# 2_INTERFACES_EXTERNAS.net
KiCad netlist of a schematic drawn in Altium Designer
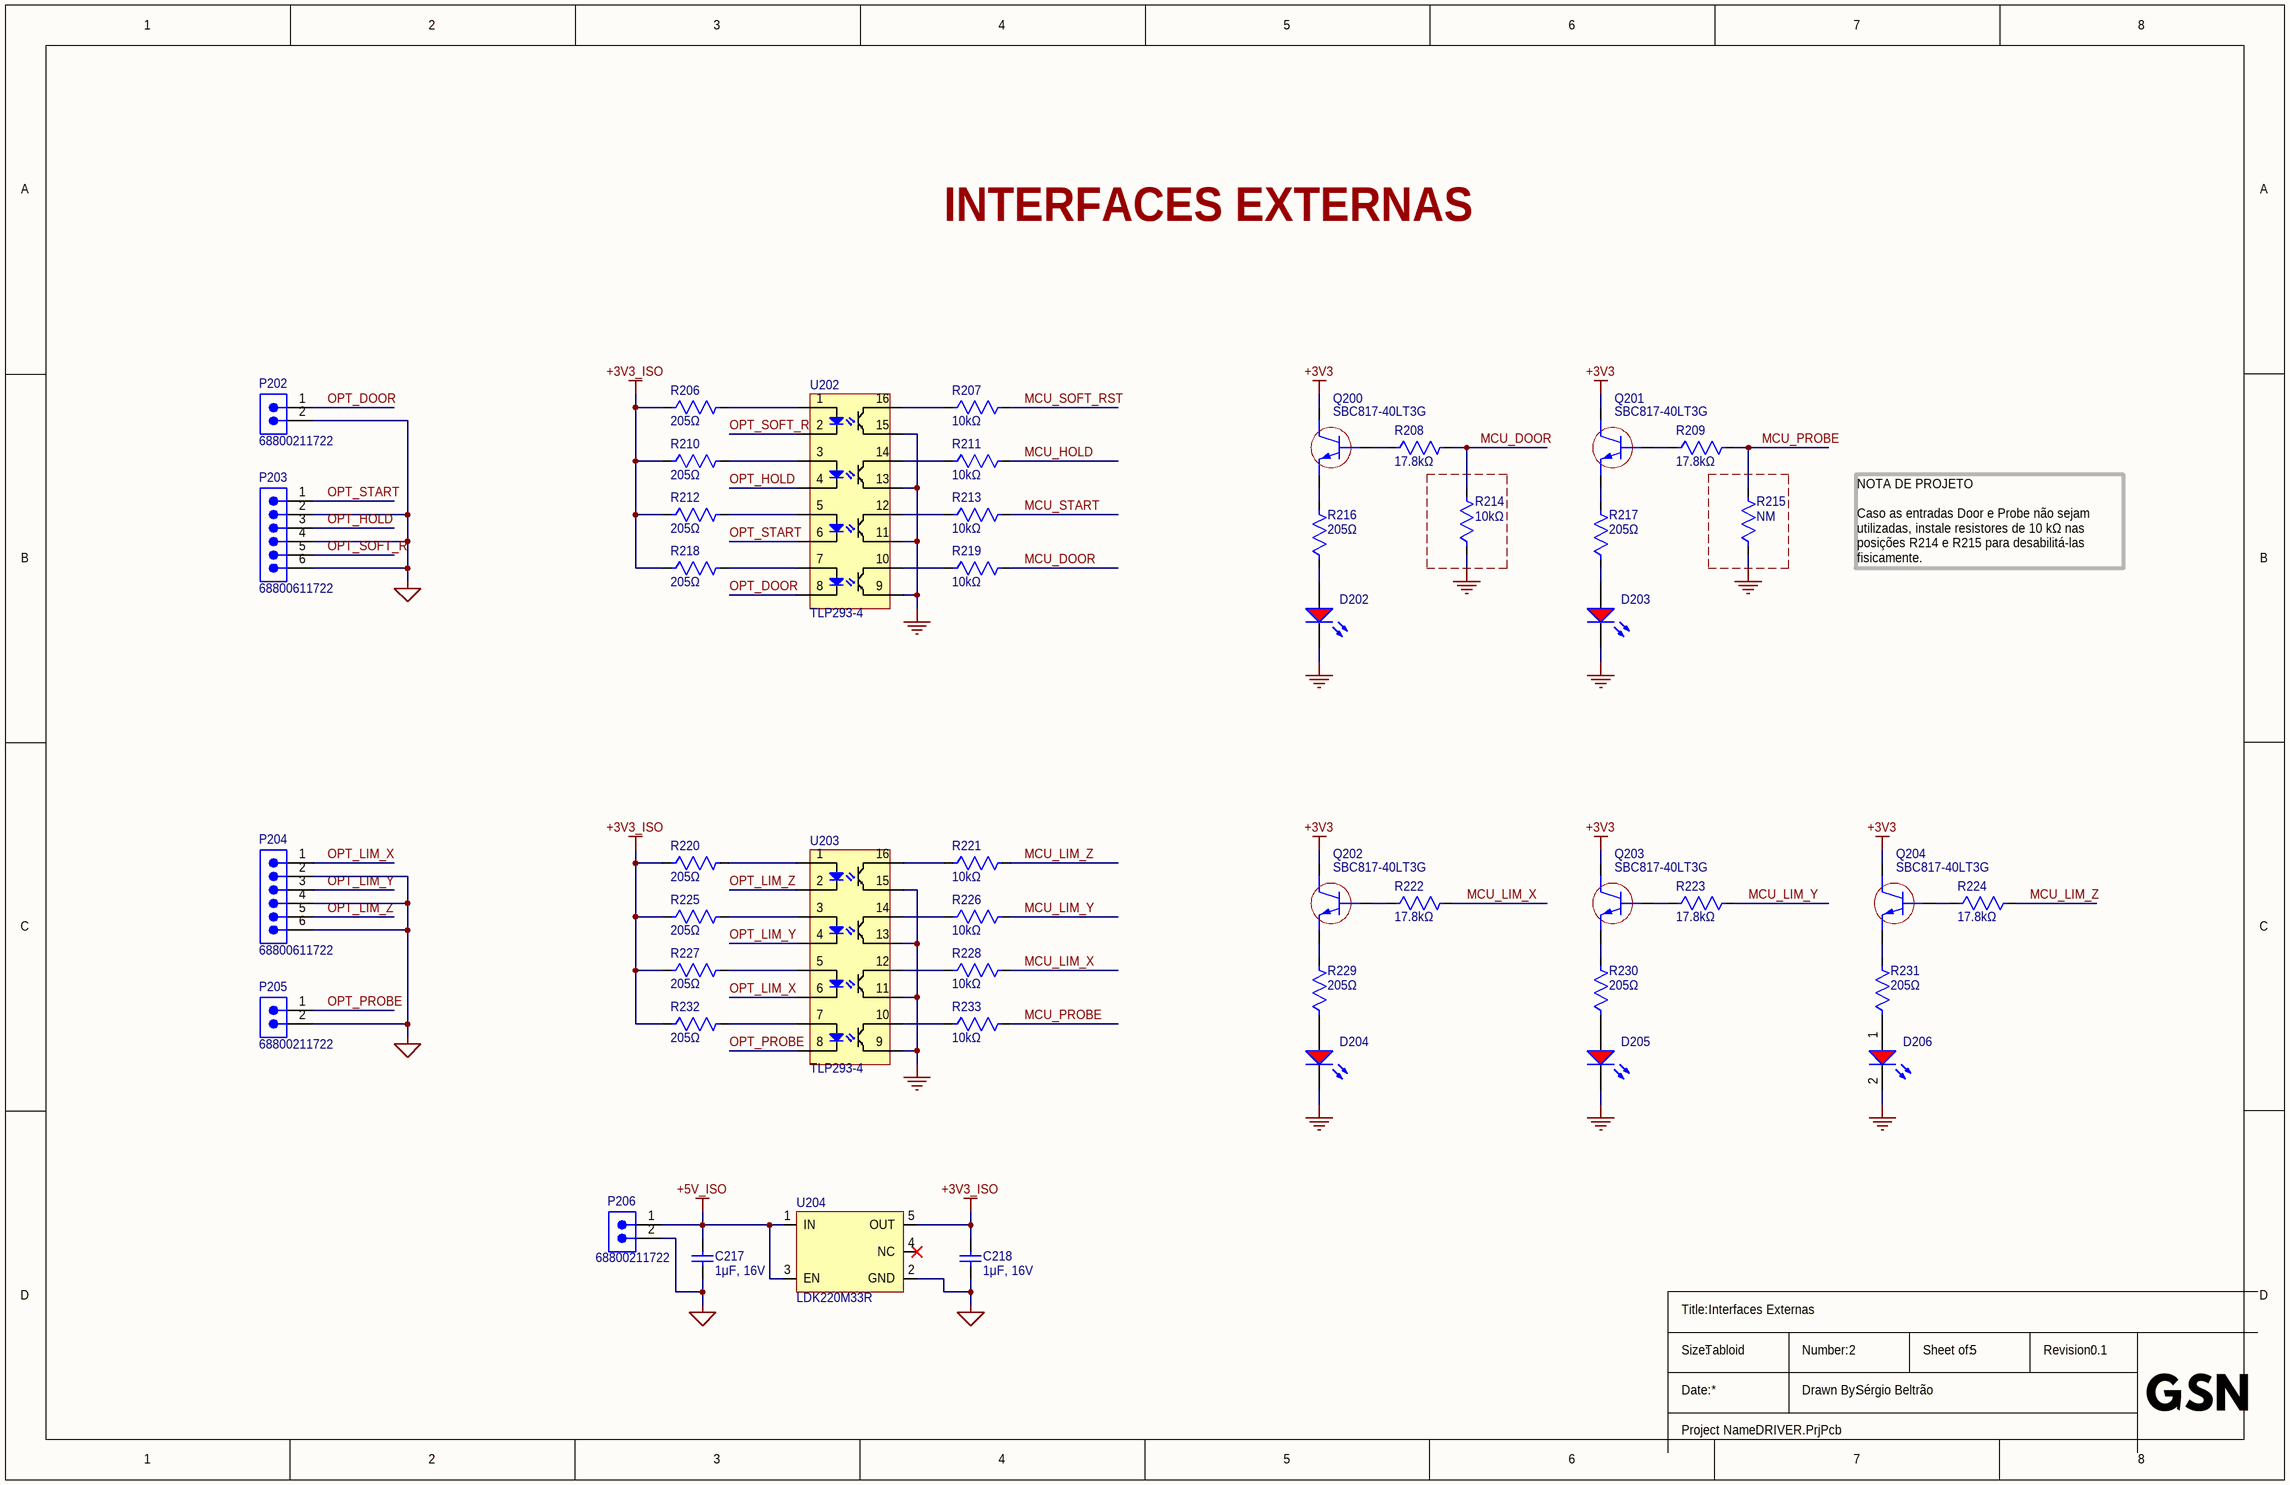
[diagram p0: 2_INTERFACES_EXTERNAS.SchDoc]

(export (version "E")
  (design (tool "Eeschema 10.0.6"))
  (components
    (comp (ref "C217")
      (value "1μF, 16V")
      (footprint "WCAP-CSGP_0603_L1.6W0.8H0.8_Wave")
      (description "WCAP-CSGP Multilayer Ceramic Chip Capacitor, General Purpose, size 0603, 1μF, 16V")
      (fields
        (field (name "MANUFACTURER PART NUMBER") "885012206052")
        (field (name "MANUFACTURER") "Wurth Elektronik")
      )
      (libsource (lib "WE - Passive Components") (part "Capacitor_Non-Polarized"))
    )
    (comp (ref "C218")
      (value "1μF, 16V")
      (footprint "WCAP-CSGP_0603_L1.6W0.8H0.8_Wave")
      (description "WCAP-CSGP Multilayer Ceramic Chip Capacitor, General Purpose, size 0603, 1μF, 16V")
      (fields
        (field (name "MANUFACTURER PART NUMBER") "885012206052")
        (field (name "MANUFACTURER") "Wurth Elektronik")
      )
      (libsource (lib "WE - Passive Components") (part "Capacitor_Non-Polarized"))
    )
    (comp (ref "D202")
      (value "Red, 2V, 140deg")
      (footprint "WL-SMCW_0603_150060xx75003")
      (description "WL-SMCW Mono-color Chip LED Waterclear, SMT, size 0603, Red, 2V, 140°")
      (fields
        (field (name "MANUFACTURER PART NUMBER") "150060RS75003")
        (field (name "MANUFACTURER") "Wurth Elektronik")
      )
      (libsource (lib "WE - Optoelectronic Components") (part "LED_Red_1A-2K"))
    )
    (comp (ref "D203")
      (value "Red, 2V, 140deg")
      (footprint "WL-SMCW_0603_150060xx75003")
      (description "WL-SMCW Mono-color Chip LED Waterclear, SMT, size 0603, Red, 2V, 140°")
      (fields
        (field (name "MANUFACTURER PART NUMBER") "150060RS75003")
        (field (name "MANUFACTURER") "Wurth Elektronik")
      )
      (libsource (lib "WE - Optoelectronic Components") (part "LED_Red_1A-2K"))
    )
    (comp (ref "D204")
      (value "Red, 2V, 140deg")
      (footprint "WL-SMCW_0603_150060xx75003")
      (description "WL-SMCW Mono-color Chip LED Waterclear, SMT, size 0603, Red, 2V, 140°")
      (fields
        (field (name "MANUFACTURER PART NUMBER") "150060RS75003")
        (field (name "MANUFACTURER") "Wurth Elektronik")
      )
      (libsource (lib "WE - Optoelectronic Components") (part "LED_Red_1A-2K"))
    )
    (comp (ref "D205")
      (value "Red, 2V, 140deg")
      (footprint "WL-SMCW_0603_150060xx75003")
      (description "WL-SMCW Mono-color Chip LED Waterclear, SMT, size 0603, Red, 2V, 140°")
      (fields
        (field (name "MANUFACTURER PART NUMBER") "150060RS75003")
        (field (name "MANUFACTURER") "Wurth Elektronik")
      )
      (libsource (lib "WE - Optoelectronic Components") (part "LED_Red_1A-2K"))
    )
    (comp (ref "D206")
      (value "Red, 2V, 140deg")
      (footprint "WL-SMCW_0603_150060xx75003")
      (description "WL-SMCW Mono-color Chip LED Waterclear, SMT, size 0603, Red, 2V, 140°")
      (fields
        (field (name "MANUFACTURER PART NUMBER") "150060RS75003")
        (field (name "MANUFACTURER") "Wurth Elektronik")
      )
      (libsource (lib "") (part "LED_Red_1A-2K_1"))
    )
    (comp (ref "P202")
      (value "68800211722")
      (footprint "68800211722")
      (description "WR-WTB “J” Type THT Male Horizontal Shrouded Header, pitch 2.5 mm, 2 pins")
      (fields (field (name "MANUFACTURER") "Wurth Elektronik"))
      (libsource (lib "WE - Electromechanical Components") (part "Header_Male_1R_02P"))
    )
    (comp (ref "P203")
      (value "68800611722")
      (footprint "68800611722")
      (description "WR-WTB “J” Type THT Male Horizontal Shrouded Header, pitch 2.5 mm, 6 pins")
      (fields (field (name "MANUFACTURER") "Wurth Elektronik"))
      (libsource (lib "WE - Electromechanical Components") (part "Header_Male_1R_06P"))
    )
    (comp (ref "P204")
      (value "68800611722")
      (footprint "68800611722")
      (description "WR-WTB “J” Type THT Male Horizontal Shrouded Header, pitch 2.5 mm, 6 pins")
      (fields (field (name "MANUFACTURER") "Wurth Elektronik"))
      (libsource (lib "WE - Electromechanical Components") (part "Header_Male_1R_06P"))
    )
    (comp (ref "P205")
      (value "68800211722")
      (footprint "68800211722")
      (description "WR-WTB “J” Type THT Male Horizontal Shrouded Header, pitch 2.5 mm, 2 pins")
      (fields (field (name "MANUFACTURER") "Wurth Elektronik"))
      (libsource (lib "WE - Electromechanical Components") (part "Header_Male_1R_02P"))
    )
    (comp (ref "P206")
      (value "68800211722")
      (footprint "68800211722")
      (description "WR-WTB “J” Type THT Male Horizontal Shrouded Header, pitch 2.5 mm, 2 pins")
      (fields (field (name "MANUFACTURER") "Wurth Elektronik"))
      (libsource (lib "WE - Electromechanical Components") (part "Header_Male_1R_02P"))
    )
    (comp (ref "Q200")
      (value "SBC817-40LT3G")
      (footprint "SOT-23-3")
      (description "TRANS NPN 45V 0.5A SOT23-3")
      (fields (field (name "MANUFACTURER") "onsemi"))
      (libsource (lib "Transistors") (part "SBC817-40LT3G"))
    )
    (comp (ref "Q201")
      (value "SBC817-40LT3G")
      (footprint "SOT-23-3")
      (description "TRANS NPN 45V 0.5A SOT23-3")
      (fields (field (name "MANUFACTURER") "onsemi"))
      (libsource (lib "Transistors") (part "SBC817-40LT3G"))
    )
    (comp (ref "Q202")
      (value "SBC817-40LT3G")
      (footprint "SOT-23-3")
      (description "TRANS NPN 45V 0.5A SOT23-3")
      (fields (field (name "MANUFACTURER") "onsemi"))
      (libsource (lib "Transistors") (part "SBC817-40LT3G"))
    )
    (comp (ref "Q203")
      (value "SBC817-40LT3G")
      (footprint "SOT-23-3")
      (description "TRANS NPN 45V 0.5A SOT23-3")
      (fields (field (name "MANUFACTURER") "onsemi"))
      (libsource (lib "Transistors") (part "SBC817-40LT3G"))
    )
    (comp (ref "Q204")
      (value "SBC817-40LT3G")
      (footprint "SOT-23-3")
      (description "TRANS NPN 45V 0.5A SOT23-3")
      (fields (field (name "MANUFACTURER") "onsemi"))
      (libsource (lib "Transistors") (part "SBC817-40LT3G"))
    )
    (comp (ref "R206")
      (value "205Ω")
      (footprint "0603-WAVE")
      (description "RES 205 OHM 1% 1/10W 0603")
      (fields
        (field (name "MANUFACTURER PART NUMBER") "RC0603FR-07205RL")
        (field (name "MANUFACTURER") "Yageo Group")
      )
      (libsource (lib "Resistors-0603-E96-Yageo") (part "RC0603FR-07205RL"))
    )
    (comp (ref "R207")
      (value "10kΩ")
      (footprint "0603-WAVE")
      (description "RES 10K OHM 1% 1/10W 0603")
      (fields
        (field (name "MANUFACTURER PART NUMBER") "RC0603FR-0710KL")
        (field (name "MANUFACTURER") "Yageo Group")
      )
      (libsource (lib "Resistors-0603-E96-Yageo") (part "RC0603FR-0710KL"))
    )
    (comp (ref "R208")
      (value "17.8kΩ")
      (footprint "0603-WAVE")
      (description "RES 17.8K OHM 1% 1/10W 0603")
      (fields
        (field (name "MANUFACTURER PART NUMBER") "RC0603FR-0717K8L")
        (field (name "MANUFACTURER") "Yageo Group")
      )
      (libsource (lib "Resistors-0603-E96-Yageo") (part "RC0603FR-0717K8L"))
    )
    (comp (ref "R209")
      (value "17.8kΩ")
      (footprint "0603-WAVE")
      (description "RES 17.8K OHM 1% 1/10W 0603")
      (fields
        (field (name "MANUFACTURER PART NUMBER") "RC0603FR-0717K8L")
        (field (name "MANUFACTURER") "Yageo Group")
      )
      (libsource (lib "Resistors-0603-E96-Yageo") (part "RC0603FR-0717K8L"))
    )
    (comp (ref "R210")
      (value "205Ω")
      (footprint "0603-WAVE")
      (description "RES 205 OHM 1% 1/10W 0603")
      (fields
        (field (name "MANUFACTURER PART NUMBER") "RC0603FR-07205RL")
        (field (name "MANUFACTURER") "Yageo Group")
      )
      (libsource (lib "Resistors-0603-E96-Yageo") (part "RC0603FR-07205RL"))
    )
    (comp (ref "R211")
      (value "10kΩ")
      (footprint "0603-WAVE")
      (description "RES 10K OHM 1% 1/10W 0603")
      (fields
        (field (name "MANUFACTURER PART NUMBER") "RC0603FR-0710KL")
        (field (name "MANUFACTURER") "Yageo Group")
      )
      (libsource (lib "Resistors-0603-E96-Yageo") (part "RC0603FR-0710KL"))
    )
    (comp (ref "R212")
      (value "205Ω")
      (footprint "0603-WAVE")
      (description "RES 205 OHM 1% 1/10W 0603")
      (fields
        (field (name "MANUFACTURER PART NUMBER") "RC0603FR-07205RL")
        (field (name "MANUFACTURER") "Yageo Group")
      )
      (libsource (lib "Resistors-0603-E96-Yageo") (part "RC0603FR-07205RL"))
    )
    (comp (ref "R213")
      (value "10kΩ")
      (footprint "0603-WAVE")
      (description "RES 10K OHM 1% 1/10W 0603")
      (fields
        (field (name "MANUFACTURER PART NUMBER") "RC0603FR-0710KL")
        (field (name "MANUFACTURER") "Yageo Group")
      )
      (libsource (lib "Resistors-0603-E96-Yageo") (part "RC0603FR-0710KL"))
    )
    (comp (ref "R214")
      (value "10kΩ")
      (footprint "0603-WAVE")
      (description "RES 10K OHM 1% 1/10W 0603")
      (fields
        (field (name "MANUFACTURER PART NUMBER") "RC0603FR-0710KL")
        (field (name "MANUFACTURER") "Yageo Group")
      )
      (libsource (lib "Resistors-0603-E96-Yageo") (part "RC0603FR-0710KL"))
    )
    (comp (ref "R215")
      (value "NM")
      (footprint "0603-WAVE")
      (description "RES 10K OHM 1% 1/10W 0603")
      (fields
        (field (name "MANUFACTURER PART NUMBER") "RC0603FR-0710KL")
        (field (name "MANUFACTURER") "Yageo Group")
      )
      (libsource (lib "Resistors-0603-E96-Yageo") (part "RC0603FR-0710KL"))
    )
    (comp (ref "R216")
      (value "205Ω")
      (footprint "0603-WAVE")
      (description "RES 205 OHM 1% 1/10W 0603")
      (fields
        (field (name "MANUFACTURER PART NUMBER") "RC0603FR-07205RL")
        (field (name "MANUFACTURER") "Yageo Group")
      )
      (libsource (lib "Resistors-0603-E96-Yageo") (part "RC0603FR-07205RL"))
    )
    (comp (ref "R217")
      (value "205Ω")
      (footprint "0603-WAVE")
      (description "RES 205 OHM 1% 1/10W 0603")
      (fields
        (field (name "MANUFACTURER PART NUMBER") "RC0603FR-07205RL")
        (field (name "MANUFACTURER") "Yageo Group")
      )
      (libsource (lib "Resistors-0603-E96-Yageo") (part "RC0603FR-07205RL"))
    )
    (comp (ref "R218")
      (value "205Ω")
      (footprint "0603-WAVE")
      (description "RES 205 OHM 1% 1/10W 0603")
      (fields
        (field (name "MANUFACTURER PART NUMBER") "RC0603FR-07205RL")
        (field (name "MANUFACTURER") "Yageo Group")
      )
      (libsource (lib "Resistors-0603-E96-Yageo") (part "RC0603FR-07205RL"))
    )
    (comp (ref "R219")
      (value "10kΩ")
      (footprint "0603-WAVE")
      (description "RES 10K OHM 1% 1/10W 0603")
      (fields
        (field (name "MANUFACTURER PART NUMBER") "RC0603FR-0710KL")
        (field (name "MANUFACTURER") "Yageo Group")
      )
      (libsource (lib "Resistors-0603-E96-Yageo") (part "RC0603FR-0710KL"))
    )
    (comp (ref "R220")
      (value "205Ω")
      (footprint "0603-WAVE")
      (description "RES 205 OHM 1% 1/10W 0603")
      (fields
        (field (name "MANUFACTURER PART NUMBER") "RC0603FR-07205RL")
        (field (name "MANUFACTURER") "Yageo Group")
      )
      (libsource (lib "Resistors-0603-E96-Yageo") (part "RC0603FR-07205RL"))
    )
    (comp (ref "R221")
      (value "10kΩ")
      (footprint "0603-WAVE")
      (description "RES 10K OHM 1% 1/10W 0603")
      (fields
        (field (name "MANUFACTURER PART NUMBER") "RC0603FR-0710KL")
        (field (name "MANUFACTURER") "Yageo Group")
      )
      (libsource (lib "Resistors-0603-E96-Yageo") (part "RC0603FR-0710KL"))
    )
    (comp (ref "R222")
      (value "17.8kΩ")
      (footprint "0603-WAVE")
      (description "RES 17.8K OHM 1% 1/10W 0603")
      (fields
        (field (name "MANUFACTURER PART NUMBER") "RC0603FR-0717K8L")
        (field (name "MANUFACTURER") "Yageo Group")
      )
      (libsource (lib "Resistors-0603-E96-Yageo") (part "RC0603FR-0717K8L"))
    )
    (comp (ref "R223")
      (value "17.8kΩ")
      (footprint "0603-WAVE")
      (description "RES 17.8K OHM 1% 1/10W 0603")
      (fields
        (field (name "MANUFACTURER PART NUMBER") "RC0603FR-0717K8L")
        (field (name "MANUFACTURER") "Yageo Group")
      )
      (libsource (lib "Resistors-0603-E96-Yageo") (part "RC0603FR-0717K8L"))
    )
    (comp (ref "R224")
      (value "17.8kΩ")
      (footprint "0603-WAVE")
      (description "RES 17.8K OHM 1% 1/10W 0603")
      (fields
        (field (name "MANUFACTURER PART NUMBER") "RC0603FR-0717K8L")
        (field (name "MANUFACTURER") "Yageo Group")
      )
      (libsource (lib "Resistors-0603-E96-Yageo") (part "RC0603FR-0717K8L"))
    )
    (comp (ref "R225")
      (value "205Ω")
      (footprint "0603-WAVE")
      (description "RES 205 OHM 1% 1/10W 0603")
      (fields
        (field (name "MANUFACTURER PART NUMBER") "RC0603FR-07205RL")
        (field (name "MANUFACTURER") "Yageo Group")
      )
      (libsource (lib "Resistors-0603-E96-Yageo") (part "RC0603FR-07205RL"))
    )
    (comp (ref "R226")
      (value "10kΩ")
      (footprint "0603-WAVE")
      (description "RES 10K OHM 1% 1/10W 0603")
      (fields
        (field (name "MANUFACTURER PART NUMBER") "RC0603FR-0710KL")
        (field (name "MANUFACTURER") "Yageo Group")
      )
      (libsource (lib "Resistors-0603-E96-Yageo") (part "RC0603FR-0710KL"))
    )
    (comp (ref "R227")
      (value "205Ω")
      (footprint "0603-WAVE")
      (description "RES 205 OHM 1% 1/10W 0603")
      (fields
        (field (name "MANUFACTURER PART NUMBER") "RC0603FR-07205RL")
        (field (name "MANUFACTURER") "Yageo Group")
      )
      (libsource (lib "Resistors-0603-E96-Yageo") (part "RC0603FR-07205RL"))
    )
    (comp (ref "R228")
      (value "10kΩ")
      (footprint "0603-WAVE")
      (description "RES 10K OHM 1% 1/10W 0603")
      (fields
        (field (name "MANUFACTURER PART NUMBER") "RC0603FR-0710KL")
        (field (name "MANUFACTURER") "Yageo Group")
      )
      (libsource (lib "Resistors-0603-E96-Yageo") (part "RC0603FR-0710KL"))
    )
    (comp (ref "R229")
      (value "205Ω")
      (footprint "0603-WAVE")
      (description "RES 205 OHM 1% 1/10W 0603")
      (fields
        (field (name "MANUFACTURER PART NUMBER") "RC0603FR-07205RL")
        (field (name "MANUFACTURER") "Yageo Group")
      )
      (libsource (lib "Resistors-0603-E96-Yageo") (part "RC0603FR-07205RL"))
    )
    (comp (ref "R230")
      (value "205Ω")
      (footprint "0603-WAVE")
      (description "RES 205 OHM 1% 1/10W 0603")
      (fields
        (field (name "MANUFACTURER PART NUMBER") "RC0603FR-07205RL")
        (field (name "MANUFACTURER") "Yageo Group")
      )
      (libsource (lib "Resistors-0603-E96-Yageo") (part "RC0603FR-07205RL"))
    )
    (comp (ref "R231")
      (value "205Ω")
      (footprint "0603-WAVE")
      (description "RES 205 OHM 1% 1/10W 0603")
      (fields
        (field (name "MANUFACTURER PART NUMBER") "RC0603FR-07205RL")
        (field (name "MANUFACTURER") "Yageo Group")
      )
      (libsource (lib "Resistors-0603-E96-Yageo") (part "RC0603FR-07205RL"))
    )
    (comp (ref "R232")
      (value "205Ω")
      (footprint "0603-WAVE")
      (description "RES 205 OHM 1% 1/10W 0603")
      (fields
        (field (name "MANUFACTURER PART NUMBER") "RC0603FR-07205RL")
        (field (name "MANUFACTURER") "Yageo Group")
      )
      (libsource (lib "Resistors-0603-E96-Yageo") (part "RC0603FR-07205RL"))
    )
    (comp (ref "R233")
      (value "10kΩ")
      (footprint "0603-WAVE")
      (description "RES 10K OHM 1% 1/10W 0603")
      (fields
        (field (name "MANUFACTURER PART NUMBER") "RC0603FR-0710KL")
        (field (name "MANUFACTURER") "Yageo Group")
      )
      (libsource (lib "Resistors-0603-E96-Yageo") (part "RC0603FR-0710KL"))
    )
    (comp (ref "U202")
      (value "TLP293-4")
      (footprint "SO-16")
      (description "OPTOISO 3.75KV 4CH TRANS 16-SO")
      (fields
        (field (name "MANUFACTURER") "Toshiba")
        (field (name "MANUFACTURER PART NUMBER") "TLP293-4(TP,E")
      )
      (libsource (lib "Optocouplers") (part "TLP293-4"))
    )
    (comp (ref "U203")
      (value "TLP293-4")
      (footprint "SO-16")
      (description "OPTOISO 3.75KV 4CH TRANS 16-SO")
      (fields
        (field (name "MANUFACTURER") "Toshiba")
        (field (name "MANUFACTURER PART NUMBER") "TLP293-4(TP,E")
      )
      (libsource (lib "Optocouplers") (part "TLP293-4"))
    )
    (comp (ref "U204")
      (value "LDK220M33R")
      (footprint "SOT-23-5")
      (description "IC REG LINEAR 3.3V 200MA SOT23-5")
      (fields (field (name "MANUFACTURER") "STMicroelectronics"))
      (libsource (lib "Voltage-Regulators") (part "LDK220M33R"))
    )
  )
  (nets
    (net (code "1") (name "+3V3") (class "Default")
      (node (ref "Q200") (pin "3") (pinfunction "C_3") (pintype "passive"))
      (node (ref "Q201") (pin "3") (pinfunction "C_3") (pintype "passive"))
      (node (ref "Q202") (pin "3") (pinfunction "C_3") (pintype "passive"))
      (node (ref "Q203") (pin "3") (pinfunction "C_3") (pintype "passive"))
      (node (ref "Q204") (pin "3") (pinfunction "C_3") (pintype "passive"))
    )
    (net (code "2") (name "+3V3_ISO") (class "Default")
      (node (ref "C218") (pin "2") (pinfunction "2_2") (pintype "passive"))
      (node (ref "R206") (pin "1") (pinfunction "1_1") (pintype "passive"))
      (node (ref "R210") (pin "1") (pinfunction "1_1") (pintype "passive"))
      (node (ref "R212") (pin "1") (pinfunction "1_1") (pintype "passive"))
      (node (ref "R218") (pin "1") (pinfunction "1_1") (pintype "passive"))
      (node (ref "R220") (pin "1") (pinfunction "1_1") (pintype "passive"))
      (node (ref "R225") (pin "1") (pinfunction "1_1") (pintype "passive"))
      (node (ref "R227") (pin "1") (pinfunction "1_1") (pintype "passive"))
      (node (ref "R232") (pin "1") (pinfunction "1_1") (pintype "passive"))
      (node (ref "U204") (pin "5") (pinfunction "OUT_5") (pintype "passive"))
    )
    (net (code "3") (name "+5V_ISO") (class "Default")
      (node (ref "C217") (pin "2") (pinfunction "2_2") (pintype "passive"))
      (node (ref "P206") (pin "1") (pinfunction "1_1") (pintype "passive"))
      (node (ref "U204") (pin "1") (pinfunction "IN_1") (pintype "passive"))
      (node (ref "U204") (pin "3") (pinfunction "EN_3") (pintype "passive"))
    )
    (net (code "4") (name "/MCU_DOOR") (class "Default")
      (node (ref "R208") (pin "2") (pinfunction "2_2") (pintype "passive"))
      (node (ref "R214") (pin "2") (pinfunction "2_2") (pintype "passive"))
      (node (ref "R219") (pin "2") (pinfunction "2_2") (pintype "passive"))
    )
    (net (code "5") (name "/MCU_HOLD") (class "Default")
      (node (ref "R211") (pin "2") (pinfunction "2_2") (pintype "passive"))
    )
    (net (code "6") (name "/MCU_LIM_X") (class "Default")
      (node (ref "R222") (pin "2") (pinfunction "2_2") (pintype "passive"))
      (node (ref "R228") (pin "2") (pinfunction "2_2") (pintype "passive"))
    )
    (net (code "7") (name "/MCU_LIM_Y") (class "Default")
      (node (ref "R223") (pin "2") (pinfunction "2_2") (pintype "passive"))
      (node (ref "R226") (pin "2") (pinfunction "2_2") (pintype "passive"))
    )
    (net (code "8") (name "/MCU_LIM_Z") (class "Default")
      (node (ref "R221") (pin "2") (pinfunction "2_2") (pintype "passive"))
      (node (ref "R224") (pin "2") (pinfunction "2_2") (pintype "passive"))
    )
    (net (code "9") (name "/MCU_PROBE") (class "Default")
      (node (ref "R209") (pin "2") (pinfunction "2_2") (pintype "passive"))
      (node (ref "R215") (pin "2") (pinfunction "2_2") (pintype "passive"))
      (node (ref "R233") (pin "2") (pinfunction "2_2") (pintype "passive"))
    )
    (net (code "10") (name "/MCU_SOFT_RST") (class "Default")
      (node (ref "R207") (pin "2") (pinfunction "2_2") (pintype "passive"))
    )
    (net (code "11") (name "/MCU_START") (class "Default")
      (node (ref "R213") (pin "2") (pinfunction "2_2") (pintype "passive"))
    )
    (net (code "12") (name "/OPT_DOOR") (class "Default")
      (node (ref "P202") (pin "1") (pinfunction "1_1") (pintype "passive"))
      (node (ref "U202") (pin "8") (pinfunction "8_8") (pintype "passive"))
    )
    (net (code "13") (name "/OPT_HOLD") (class "Default")
      (node (ref "P203") (pin "3") (pinfunction "3_3") (pintype "passive"))
      (node (ref "U202") (pin "4") (pinfunction "4_4") (pintype "passive"))
    )
    (net (code "14") (name "/OPT_LIM_X") (class "Default")
      (node (ref "P204") (pin "1") (pinfunction "1_1") (pintype "passive"))
      (node (ref "U203") (pin "6") (pinfunction "6_6") (pintype "passive"))
    )
    (net (code "15") (name "/OPT_LIM_Y") (class "Default")
      (node (ref "P204") (pin "3") (pinfunction "3_3") (pintype "passive"))
      (node (ref "U203") (pin "4") (pinfunction "4_4") (pintype "passive"))
    )
    (net (code "16") (name "/OPT_LIM_Z") (class "Default")
      (node (ref "P204") (pin "5") (pinfunction "5_5") (pintype "passive"))
      (node (ref "U203") (pin "2") (pinfunction "2_2") (pintype "passive"))
    )
    (net (code "17") (name "/OPT_PROBE") (class "Default")
      (node (ref "P205") (pin "1") (pinfunction "1_1") (pintype "passive"))
      (node (ref "U203") (pin "8") (pinfunction "8_8") (pintype "passive"))
    )
    (net (code "18") (name "/OPT_SOFT_R") (class "Default")
      (node (ref "P203") (pin "5") (pinfunction "5_5") (pintype "passive"))
      (node (ref "U202") (pin "2") (pinfunction "2_2") (pintype "passive"))
    )
    (net (code "19") (name "/OPT_START") (class "Default")
      (node (ref "P203") (pin "1") (pinfunction "1_1") (pintype "passive"))
      (node (ref "U202") (pin "6") (pinfunction "6_6") (pintype "passive"))
    )
    (net (code "20") (name "GND") (class "Default")
      (node (ref "D202") (pin "2") (pinfunction "K_2") (pintype "passive"))
      (node (ref "D203") (pin "2") (pinfunction "K_2") (pintype "passive"))
      (node (ref "D204") (pin "2") (pinfunction "K_2") (pintype "passive"))
      (node (ref "D205") (pin "2") (pinfunction "K_2") (pintype "passive"))
      (node (ref "D206") (pin "2") (pinfunction "K_2") (pintype "passive"))
      (node (ref "R214") (pin "1") (pinfunction "1_1") (pintype "passive"))
      (node (ref "R215") (pin "1") (pinfunction "1_1") (pintype "passive"))
      (node (ref "U202") (pin "11") (pinfunction "11_11") (pintype "passive"))
      (node (ref "U202") (pin "13") (pinfunction "13_13") (pintype "passive"))
      (node (ref "U202") (pin "15") (pinfunction "15_15") (pintype "passive"))
      (node (ref "U202") (pin "9") (pinfunction "9_9") (pintype "passive"))
      (node (ref "U203") (pin "11") (pinfunction "11_11") (pintype "passive"))
      (node (ref "U203") (pin "13") (pinfunction "13_13") (pintype "passive"))
      (node (ref "U203") (pin "15") (pinfunction "15_15") (pintype "passive"))
      (node (ref "U203") (pin "9") (pinfunction "9_9") (pintype "passive"))
    )
    (net (code "21") (name "GND_ISO") (class "Default")
      (node (ref "C217") (pin "1") (pinfunction "1_1") (pintype "passive"))
      (node (ref "C218") (pin "1") (pinfunction "1_1") (pintype "passive"))
      (node (ref "P202") (pin "2") (pinfunction "2_2") (pintype "passive"))
      (node (ref "P203") (pin "2") (pinfunction "2_2") (pintype "passive"))
      (node (ref "P203") (pin "4") (pinfunction "4_4") (pintype "passive"))
      (node (ref "P203") (pin "6") (pinfunction "6_6") (pintype "passive"))
      (node (ref "P204") (pin "2") (pinfunction "2_2") (pintype "passive"))
      (node (ref "P204") (pin "4") (pinfunction "4_4") (pintype "passive"))
      (node (ref "P204") (pin "6") (pinfunction "6_6") (pintype "passive"))
      (node (ref "P205") (pin "2") (pinfunction "2_2") (pintype "passive"))
      (node (ref "P206") (pin "2") (pinfunction "2_2") (pintype "passive"))
      (node (ref "U204") (pin "2") (pinfunction "GND_2") (pintype "passive"))
    )
    (net (code "22") (name "Net-(D202-A)") (class "Default")
      (node (ref "D202") (pin "1") (pinfunction "A_1") (pintype "passive"))
      (node (ref "R216") (pin "1") (pinfunction "1_1") (pintype "passive"))
    )
    (net (code "23") (name "Net-(D203-A)") (class "Default")
      (node (ref "D203") (pin "1") (pinfunction "A_1") (pintype "passive"))
      (node (ref "R217") (pin "1") (pinfunction "1_1") (pintype "passive"))
    )
    (net (code "24") (name "Net-(D204-A)") (class "Default")
      (node (ref "D204") (pin "1") (pinfunction "A_1") (pintype "passive"))
      (node (ref "R229") (pin "1") (pinfunction "1_1") (pintype "passive"))
    )
    (net (code "25") (name "Net-(D205-A)") (class "Default")
      (node (ref "D205") (pin "1") (pinfunction "A_1") (pintype "passive"))
      (node (ref "R230") (pin "1") (pinfunction "1_1") (pintype "passive"))
    )
    (net (code "26") (name "Net-(D206-A)") (class "Default")
      (node (ref "D206") (pin "1") (pinfunction "A_1") (pintype "passive"))
      (node (ref "R231") (pin "1") (pinfunction "1_1") (pintype "passive"))
    )
    (net (code "27") (name "Net-(Q200-B)") (class "Default")
      (node (ref "Q200") (pin "1") (pinfunction "B_1") (pintype "passive"))
      (node (ref "R208") (pin "1") (pinfunction "1_1") (pintype "passive"))
    )
    (net (code "28") (name "Net-(Q200-E)") (class "Default")
      (node (ref "Q200") (pin "2") (pinfunction "E_2") (pintype "passive"))
      (node (ref "R216") (pin "2") (pinfunction "2_2") (pintype "passive"))
    )
    (net (code "29") (name "Net-(Q201-B)") (class "Default")
      (node (ref "Q201") (pin "1") (pinfunction "B_1") (pintype "passive"))
      (node (ref "R209") (pin "1") (pinfunction "1_1") (pintype "passive"))
    )
    (net (code "30") (name "Net-(Q201-E)") (class "Default")
      (node (ref "Q201") (pin "2") (pinfunction "E_2") (pintype "passive"))
      (node (ref "R217") (pin "2") (pinfunction "2_2") (pintype "passive"))
    )
    (net (code "31") (name "Net-(Q202-B)") (class "Default")
      (node (ref "Q202") (pin "1") (pinfunction "B_1") (pintype "passive"))
      (node (ref "R222") (pin "1") (pinfunction "1_1") (pintype "passive"))
    )
    (net (code "32") (name "Net-(Q202-E)") (class "Default")
      (node (ref "Q202") (pin "2") (pinfunction "E_2") (pintype "passive"))
      (node (ref "R229") (pin "2") (pinfunction "2_2") (pintype "passive"))
    )
    (net (code "33") (name "Net-(Q203-B)") (class "Default")
      (node (ref "Q203") (pin "1") (pinfunction "B_1") (pintype "passive"))
      (node (ref "R223") (pin "1") (pinfunction "1_1") (pintype "passive"))
    )
    (net (code "34") (name "Net-(Q203-E)") (class "Default")
      (node (ref "Q203") (pin "2") (pinfunction "E_2") (pintype "passive"))
      (node (ref "R230") (pin "2") (pinfunction "2_2") (pintype "passive"))
    )
    (net (code "35") (name "Net-(Q204-B)") (class "Default")
      (node (ref "Q204") (pin "1") (pinfunction "B_1") (pintype "passive"))
      (node (ref "R224") (pin "1") (pinfunction "1_1") (pintype "passive"))
    )
    (net (code "36") (name "Net-(Q204-E)") (class "Default")
      (node (ref "Q204") (pin "2") (pinfunction "E_2") (pintype "passive"))
      (node (ref "R231") (pin "2") (pinfunction "2_2") (pintype "passive"))
    )
    (net (code "37") (name "Net-(R206-Pad2)") (class "Default")
      (node (ref "R206") (pin "2") (pinfunction "2_2") (pintype "passive"))
      (node (ref "U202") (pin "1") (pinfunction "1_1") (pintype "passive"))
    )
    (net (code "38") (name "Net-(R207-Pad1)") (class "Default")
      (node (ref "R207") (pin "1") (pinfunction "1_1") (pintype "passive"))
      (node (ref "U202") (pin "16") (pinfunction "16_16") (pintype "passive"))
    )
    (net (code "39") (name "Net-(R210-Pad2)") (class "Default")
      (node (ref "R210") (pin "2") (pinfunction "2_2") (pintype "passive"))
      (node (ref "U202") (pin "3") (pinfunction "3_3") (pintype "passive"))
    )
    (net (code "40") (name "Net-(R211-Pad1)") (class "Default")
      (node (ref "R211") (pin "1") (pinfunction "1_1") (pintype "passive"))
      (node (ref "U202") (pin "14") (pinfunction "14_14") (pintype "passive"))
    )
    (net (code "41") (name "Net-(R212-Pad2)") (class "Default")
      (node (ref "R212") (pin "2") (pinfunction "2_2") (pintype "passive"))
      (node (ref "U202") (pin "5") (pinfunction "5_5") (pintype "passive"))
    )
    (net (code "42") (name "Net-(R213-Pad1)") (class "Default")
      (node (ref "R213") (pin "1") (pinfunction "1_1") (pintype "passive"))
      (node (ref "U202") (pin "12") (pinfunction "12_12") (pintype "passive"))
    )
    (net (code "43") (name "Net-(R218-Pad2)") (class "Default")
      (node (ref "R218") (pin "2") (pinfunction "2_2") (pintype "passive"))
      (node (ref "U202") (pin "7") (pinfunction "7_7") (pintype "passive"))
    )
    (net (code "44") (name "Net-(R219-Pad1)") (class "Default")
      (node (ref "R219") (pin "1") (pinfunction "1_1") (pintype "passive"))
      (node (ref "U202") (pin "10") (pinfunction "10_10") (pintype "passive"))
    )
    (net (code "45") (name "Net-(R220-Pad2)") (class "Default")
      (node (ref "R220") (pin "2") (pinfunction "2_2") (pintype "passive"))
      (node (ref "U203") (pin "1") (pinfunction "1_1") (pintype "passive"))
    )
    (net (code "46") (name "Net-(R221-Pad1)") (class "Default")
      (node (ref "R221") (pin "1") (pinfunction "1_1") (pintype "passive"))
      (node (ref "U203") (pin "16") (pinfunction "16_16") (pintype "passive"))
    )
    (net (code "47") (name "Net-(R225-Pad2)") (class "Default")
      (node (ref "R225") (pin "2") (pinfunction "2_2") (pintype "passive"))
      (node (ref "U203") (pin "3") (pinfunction "3_3") (pintype "passive"))
    )
    (net (code "48") (name "Net-(R226-Pad1)") (class "Default")
      (node (ref "R226") (pin "1") (pinfunction "1_1") (pintype "passive"))
      (node (ref "U203") (pin "14") (pinfunction "14_14") (pintype "passive"))
    )
    (net (code "49") (name "Net-(R227-Pad2)") (class "Default")
      (node (ref "R227") (pin "2") (pinfunction "2_2") (pintype "passive"))
      (node (ref "U203") (pin "5") (pinfunction "5_5") (pintype "passive"))
    )
    (net (code "50") (name "Net-(R228-Pad1)") (class "Default")
      (node (ref "R228") (pin "1") (pinfunction "1_1") (pintype "passive"))
      (node (ref "U203") (pin "12") (pinfunction "12_12") (pintype "passive"))
    )
    (net (code "51") (name "Net-(R232-Pad2)") (class "Default")
      (node (ref "R232") (pin "2") (pinfunction "2_2") (pintype "passive"))
      (node (ref "U203") (pin "7") (pinfunction "7_7") (pintype "passive"))
    )
    (net (code "52") (name "Net-(R233-Pad1)") (class "Default")
      (node (ref "R233") (pin "1") (pinfunction "1_1") (pintype "passive"))
      (node (ref "U203") (pin "10") (pinfunction "10_10") (pintype "passive"))
    )
    (net (code "53") (name "unconnected-(U204-NC-Pad4)") (class "Default")
      (node (ref "U204") (pin "4") (pinfunction "NC_4") (pintype "passive+no_connect"))
    )
  )
)
